# PiPowerRF.net
KiCad netlist of a schematic drawn in EAGLE
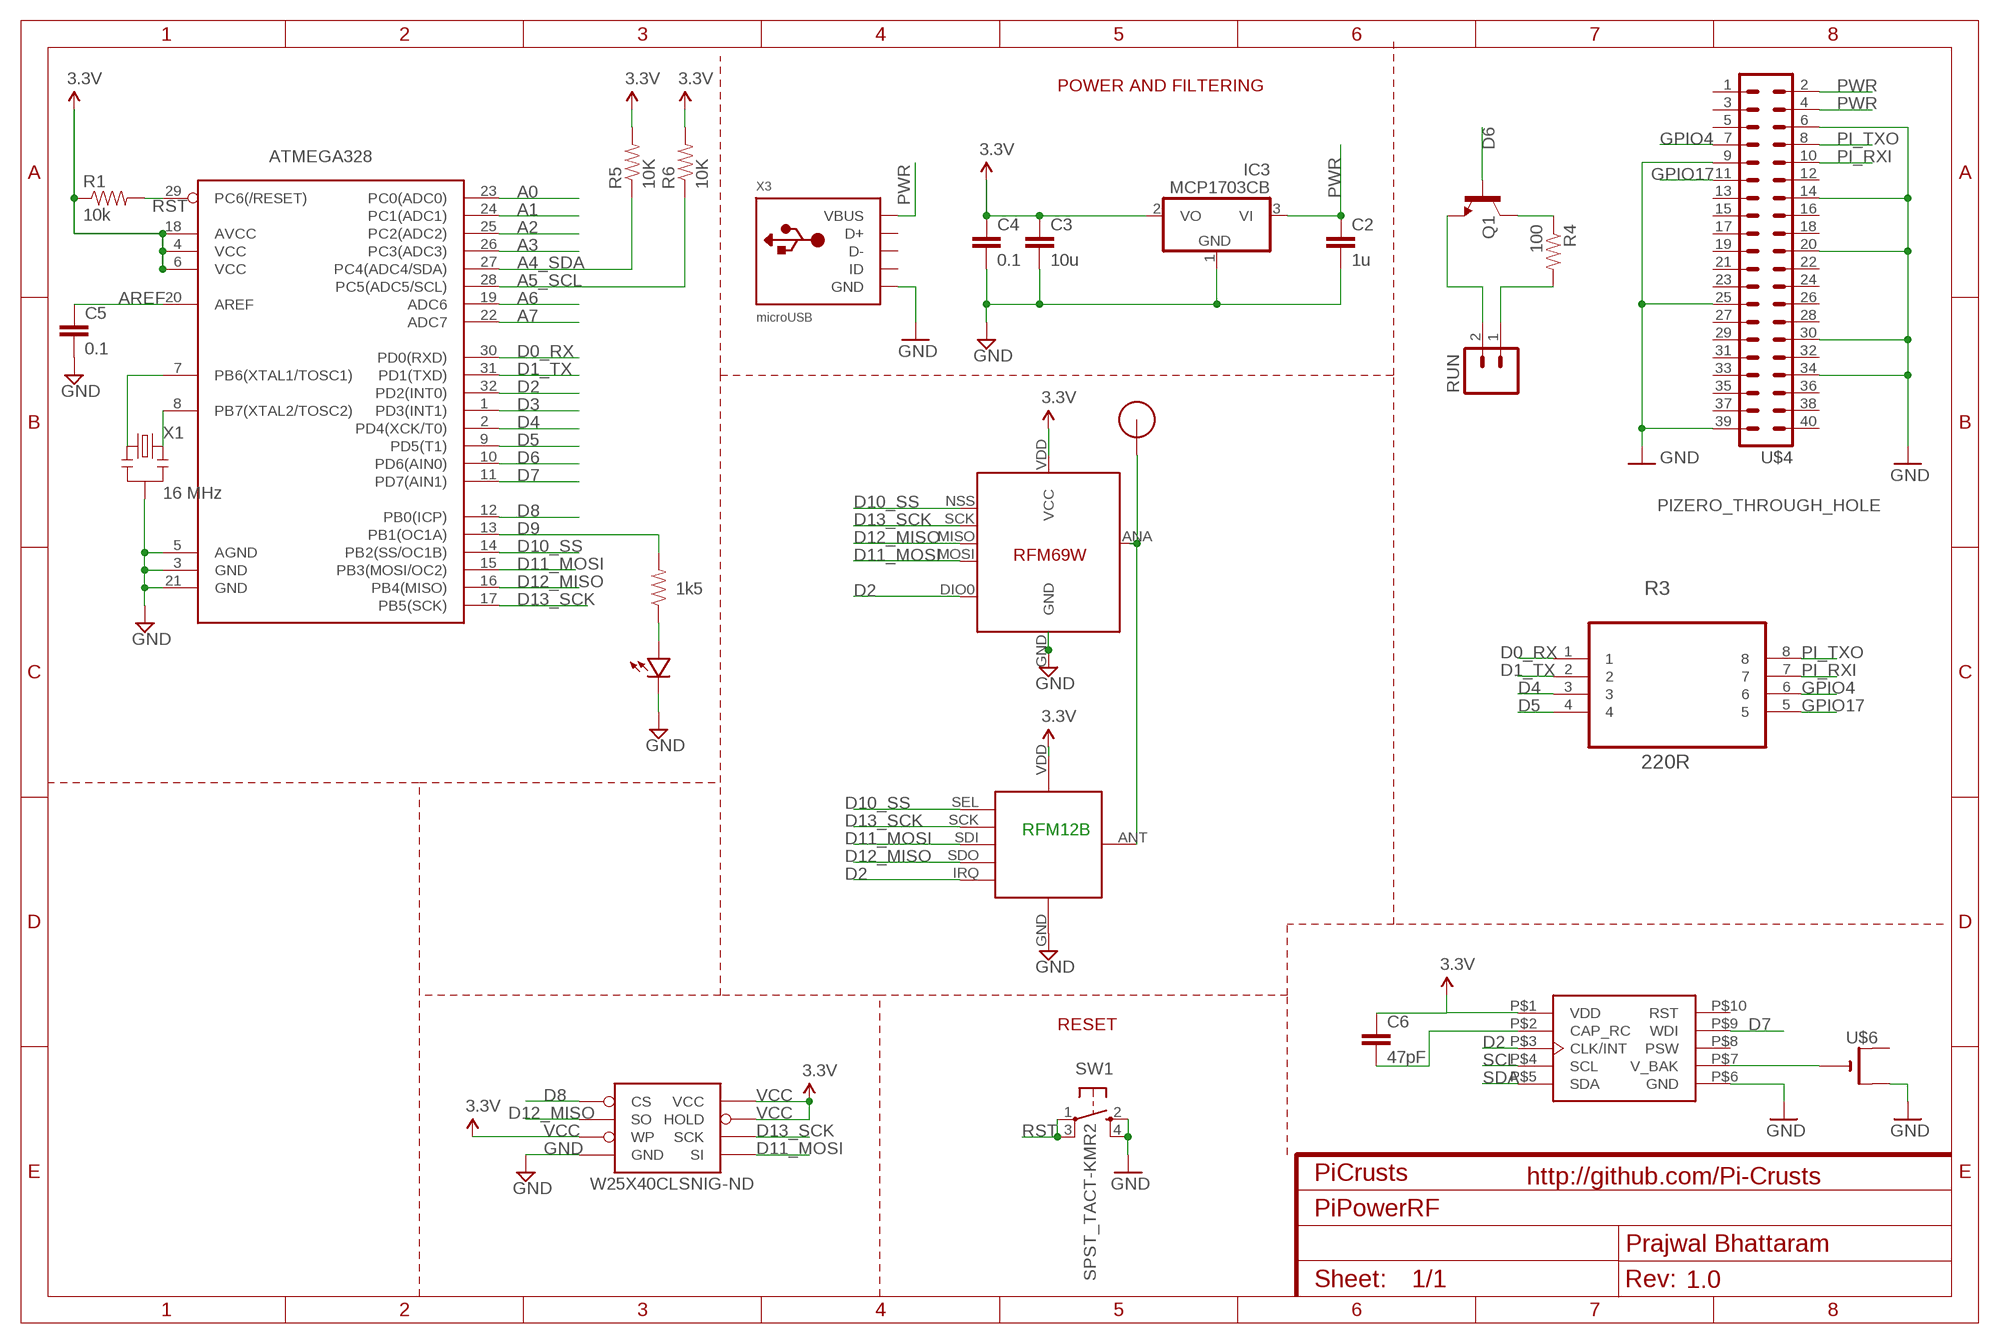
[diagram p0: schematic, sheet 1]

(export (version "E")
  (design (tool "Eeschema 10.0.6"))
  (components
    (comp (ref "ATMEGA328")
      (value "ATMega-328")
      (footprint "eagle-import:TQFP32-08")
      (libsource (lib "eagle-import") (part "ATMEGA168/328TQFP32"))
    )
    (comp (ref "C2")
      (value "1u")
      (footprint "eagle-import:0603-CAP")
      (libsource (lib "eagle-import") (part "CAP0603-CAP"))
    )
    (comp (ref "C3")
      (value "10u")
      (footprint "eagle-import:0805-CAP")
      (libsource (lib "eagle-import") (part "CAP0805-CAP"))
    )
    (comp (ref "C4")
      (value "0.1")
      (footprint "eagle-import:0603-CAP")
      (libsource (lib "eagle-import") (part "CAP0603-CAP"))
    )
    (comp (ref "C5")
      (value "0.1")
      (footprint "eagle-import:0603-CAP")
      (libsource (lib "eagle-import") (part "CAP0603-CAP"))
    )
    (comp (ref "C6")
      (value "47pF")
      (footprint "eagle-import:0402-CAP")
      (libsource (lib "eagle-import") (part "SparkFun-Capacitors_CAP0402-CAP"))
    )
    (comp (ref "IC3")
      (value "MCP1703CB")
      (footprint "eagle-import:SOT23")
      (libsource (lib "eagle-import") (part "MCP1703CB"))
    )
    (comp (ref "Q1")
      (value "MMBT2222A")
      (footprint "eagle-import:SOT23-3")
      (libsource (lib "eagle-import") (part "TRANSISTOR_NPNMMBT2222A"))
    )
    (comp (ref "R1")
      (value "10k")
      (footprint "eagle-import:0603-RES")
      (libsource (lib "eagle-import") (part "RESISTOR0603-RES"))
    )
    (comp (ref "R2")
      (value "1k5")
      (footprint "eagle-import:0603-RES")
      (libsource (lib "eagle-import") (part "RESISTOR0603-RES"))
    )
    (comp (ref "R3")
      (value "220R")
      (footprint "eagle-import:RESCAXE80P320X160X60-8N")
      (fields (field (name "MPN") "EXB38V221JV") (field (name "TOLERANCE") "±5 %"))
      (libsource (lib "eagle-import") (part "EXB38V221JV"))
    )
    (comp (ref "R4")
      (value "100")
      (footprint "eagle-import:0402-RES")
      (libsource (lib "eagle-import") (part "SparkFun-Passives_RESISTOR0402-RES"))
    )
    (comp (ref "R5")
      (value "10K")
      (footprint "eagle-import:0603-RES")
      (libsource (lib "eagle-import") (part "RESISTOR0603"))
    )
    (comp (ref "R6")
      (value "10K")
      (footprint "eagle-import:0603-RES")
      (libsource (lib "eagle-import") (part "RESISTOR0603"))
    )
    (comp (ref "RFM12B")
      (value "RFM12B_MINPADS")
      (footprint "eagle-import:RFM12B-MINPADS")
      (libsource (lib "eagle-import") (part "RFM12B_MINPADS"))
    )
    (comp (ref "RUN")
      (value "M021X02_NO_SILK")
      (footprint "eagle-import:1X02_NO_SILK")
      (libsource (lib "eagle-import") (part "M021X02_NO_SILK"))
    )
    (comp (ref "SW1")
      (value "SPST_TACT-KMR2")
      (footprint "eagle-import:KMR2")
      (libsource (lib "eagle-import") (part "SPST_TACT-KMR2"))
    )
    (comp (ref "U$1")
      (value "RFM12B_ANTENNA")
      (footprint "eagle-import:RFM12B-ANTENNA")
      (libsource (lib "eagle-import") (part "RFM12B_ANTENNA"))
    )
    (comp (ref "U$2")
      (value "LED0603")
      (footprint "eagle-import:0603-LED")
      (libsource (lib "eagle-import") (part "LED0603"))
    )
    (comp (ref "U$4")
      (value "PIZERO_THROUGH_HOLE")
      (footprint "eagle-import:PIZERO_THOUGH_HOLE")
      (libsource (lib "eagle-import") (part "PIZERO_THROUGH_HOLE"))
    )
    (comp (ref "U$5")
      (value "RFM69")
      (footprint "eagle-import:RFM69W-MINPADS")
      (libsource (lib "eagle-import") (part "RFM69"))
    )
    (comp (ref "U$6")
      (value "CR1220SMT")
      (footprint "eagle-import:CR1220-SMD")
      (libsource (lib "eagle-import") (part "CR1220SMT"))
    )
    (comp (ref "W25X40CLSNIG-ND")
      (value "AT25F512BWIDE_5.3MM")
      (footprint "eagle-import:SO08WIDE")
      (libsource (lib "eagle-import") (part "AT25F512BWIDE_5.3MM"))
    )
    (comp (ref "X1")
      (value "16 MHz")
      (footprint "eagle-import:RESONATOR-SMD")
      (libsource (lib "eagle-import") (part "RESONATORSMD"))
    )
    (comp (ref "X2")
      (value "MC-RTC-RV-1805-C3-I2C")
      (footprint "eagle-import:MC-RTC-C3")
      (libsource (lib "eagle-import") (part "MC-RTC-RV-1805-C3-I2C"))
    )
    (comp (ref "X3")
      (value "microUSB")
      (footprint "eagle-import:4UCONN_20329_V2")
      (libsource (lib "eagle-import") (part "USB_MICRO_20329_V2"))
    )
  )
  (nets
    (net (code "1") (name "/A0") (class "Default")
      (node (ref "ATMEGA328") (pin "23") (pinfunction "PC0(ADC0)_23") (pintype "bidirectional"))
    )
    (net (code "2") (name "/A1") (class "Default")
      (node (ref "ATMEGA328") (pin "24") (pinfunction "PC1(ADC1)_24") (pintype "bidirectional"))
    )
    (net (code "3") (name "/A2") (class "Default")
      (node (ref "ATMEGA328") (pin "25") (pinfunction "PC2(ADC2)_25") (pintype "bidirectional"))
    )
    (net (code "4") (name "/A3") (class "Default")
      (node (ref "ATMEGA328") (pin "26") (pinfunction "PC3(ADC3)_26") (pintype "bidirectional"))
    )
    (net (code "5") (name "/A4_SDA") (class "Default")
      (node (ref "ATMEGA328") (pin "27") (pinfunction "PC4(ADC4/SDA)_27") (pintype "bidirectional"))
      (node (ref "R5") (pin "1") (pinfunction "1_1") (pintype "passive"))
    )
    (net (code "6") (name "/A5_SCL") (class "Default")
      (node (ref "ATMEGA328") (pin "28") (pinfunction "PC5(ADC5/SCL)_28") (pintype "bidirectional"))
      (node (ref "R6") (pin "1") (pinfunction "1_1") (pintype "passive"))
    )
    (net (code "7") (name "/A6") (class "Default")
      (node (ref "ATMEGA328") (pin "19") (pinfunction "ADC6_19") (pintype "bidirectional"))
    )
    (net (code "8") (name "/A7") (class "Default")
      (node (ref "ATMEGA328") (pin "22") (pinfunction "ADC7_22") (pintype "bidirectional"))
    )
    (net (code "9") (name "/AREF") (class "Default")
      (node (ref "ATMEGA328") (pin "20") (pinfunction "AREF_20") (pintype "bidirectional"))
      (node (ref "C5") (pin "1") (pinfunction "1_1") (pintype "passive"))
    )
    (net (code "10") (name "/D0_RX") (class "Default")
      (node (ref "ATMEGA328") (pin "30") (pinfunction "PD0(RXD)_30") (pintype "bidirectional"))
      (node (ref "R3") (pin "1") (pinfunction "1_1") (pintype "passive"))
    )
    (net (code "11") (name "/D1_TX") (class "Default")
      (node (ref "ATMEGA328") (pin "31") (pinfunction "PD1(TXD)_31") (pintype "bidirectional"))
      (node (ref "R3") (pin "2") (pinfunction "2_2") (pintype "passive"))
    )
    (net (code "12") (name "/D2") (class "Default")
      (node (ref "ATMEGA328") (pin "32") (pinfunction "PD2(INT0)_32") (pintype "bidirectional"))
      (node (ref "RFM12B") (pin "IRQ") (pinfunction "IRQ_IRQ") (pintype "bidirectional"))
      (node (ref "U$5") (pin "DIO0") (pinfunction "DIO0_DIO0") (pintype "open_collector"))
      (node (ref "X2") (pin "P$3") (pinfunction "CLK/INT_P$3") (pintype "output"))
    )
    (net (code "13") (name "/D3") (class "Default")
      (node (ref "ATMEGA328") (pin "1") (pinfunction "PD3(INT1)_1") (pintype "bidirectional"))
    )
    (net (code "14") (name "/D4") (class "Default")
      (node (ref "ATMEGA328") (pin "2") (pinfunction "PD4(XCK/T0)_2") (pintype "bidirectional"))
      (node (ref "R3") (pin "3") (pinfunction "3_3") (pintype "passive"))
    )
    (net (code "15") (name "/D5") (class "Default")
      (node (ref "ATMEGA328") (pin "9") (pinfunction "PD5(T1)_9") (pintype "bidirectional"))
      (node (ref "R3") (pin "4") (pinfunction "4_4") (pintype "passive"))
    )
    (net (code "16") (name "/D6") (class "Default")
      (node (ref "ATMEGA328") (pin "10") (pinfunction "PD6(AIN0)_10") (pintype "bidirectional"))
      (node (ref "Q1") (pin "1") (pinfunction "B_1") (pintype "passive"))
    )
    (net (code "17") (name "/D7") (class "Default")
      (node (ref "ATMEGA328") (pin "11") (pinfunction "PD7(AIN1)_11") (pintype "bidirectional"))
      (node (ref "X2") (pin "P$9") (pinfunction "WDI_P$9") (pintype "bidirectional"))
    )
    (net (code "18") (name "/D8") (class "Default")
      (node (ref "ATMEGA328") (pin "12") (pinfunction "PB0(ICP)_12") (pintype "bidirectional"))
      (node (ref "W25X40CLSNIG-ND") (pin "1") (pinfunction "CS_1") (pintype "bidirectional"))
    )
    (net (code "19") (name "/D9") (class "Default")
      (node (ref "ATMEGA328") (pin "13") (pinfunction "PB1(OC1A)_13") (pintype "bidirectional"))
      (node (ref "R2") (pin "2") (pinfunction "2_2") (pintype "passive"))
    )
    (net (code "20") (name "/D10_SS") (class "Default")
      (node (ref "ATMEGA328") (pin "14") (pinfunction "PB2(SS/OC1B)_14") (pintype "bidirectional"))
      (node (ref "RFM12B") (pin "SEL") (pinfunction "SEL_SEL") (pintype "bidirectional"))
      (node (ref "U$5") (pin "NSS") (pinfunction "SEL_NSS") (pintype "input"))
    )
    (net (code "21") (name "/D11_MOSI") (class "Default")
      (node (ref "ATMEGA328") (pin "15") (pinfunction "PB3(MOSI/OC2)_15") (pintype "bidirectional"))
      (node (ref "RFM12B") (pin "SDI") (pinfunction "SDI/MOSI_SDI") (pintype "bidirectional"))
      (node (ref "U$5") (pin "MOSI") (pinfunction "MOSI_MOSI") (pintype "output"))
      (node (ref "W25X40CLSNIG-ND") (pin "5") (pinfunction "SI_5") (pintype "bidirectional"))
    )
    (net (code "22") (name "/D12_MISO") (class "Default")
      (node (ref "ATMEGA328") (pin "16") (pinfunction "PB4(MISO)_16") (pintype "bidirectional"))
      (node (ref "RFM12B") (pin "SDO") (pinfunction "SDO/MISO_SDO") (pintype "bidirectional"))
      (node (ref "U$5") (pin "MISO") (pinfunction "MISO_MISO") (pintype "input"))
      (node (ref "W25X40CLSNIG-ND") (pin "2") (pinfunction "SO_2") (pintype "bidirectional"))
    )
    (net (code "23") (name "/D13_SCK") (class "Default")
      (node (ref "ATMEGA328") (pin "17") (pinfunction "PB5(SCK)_17") (pintype "bidirectional"))
      (node (ref "RFM12B") (pin "SCK") (pinfunction "SCK_SCK") (pintype "bidirectional"))
      (node (ref "U$5") (pin "SCK") (pinfunction "SCK_SCK") (pintype "input"))
      (node (ref "W25X40CLSNIG-ND") (pin "6") (pinfunction "SCK_6") (pintype "bidirectional"))
    )
    (net (code "24") (name "/GPIO4") (class "Default")
      (node (ref "R3") (pin "6") (pinfunction "6_6") (pintype "passive"))
      (node (ref "U$4") (pin "7") (pinfunction "7_7") (pintype "passive"))
    )
    (net (code "25") (name "/GPIO17") (class "Default")
      (node (ref "R3") (pin "5") (pinfunction "5_5") (pintype "passive"))
      (node (ref "U$4") (pin "11") (pinfunction "11_11") (pintype "passive"))
    )
    (net (code "26") (name "/PI_RXI") (class "Default")
      (node (ref "R3") (pin "7") (pinfunction "7_7") (pintype "passive"))
      (node (ref "U$4") (pin "10") (pinfunction "10_10") (pintype "passive"))
    )
    (net (code "27") (name "/PI_TXO") (class "Default")
      (node (ref "R3") (pin "8") (pinfunction "8_8") (pintype "passive"))
      (node (ref "U$4") (pin "8") (pinfunction "8_8") (pintype "passive"))
    )
    (net (code "28") (name "/PWR") (class "Default")
      (node (ref "C2") (pin "1") (pinfunction "1_1") (pintype "passive"))
      (node (ref "IC3") (pin "3") (pinfunction "VI_3") (pintype "input"))
      (node (ref "U$4") (pin "2") (pinfunction "2_2") (pintype "passive"))
      (node (ref "U$4") (pin "4") (pinfunction "4_4") (pintype "passive"))
      (node (ref "X3") (pin "VBUS") (pinfunction "VBUS_VBUS") (pintype "power_in"))
    )
    (net (code "29") (name "/RST") (class "Default")
      (node (ref "ATMEGA328") (pin "29") (pinfunction "PC6(/RESET)_29") (pintype "bidirectional"))
      (node (ref "R1") (pin "2") (pinfunction "2_2") (pintype "passive"))
      (node (ref "SW1") (pin "1") (pinfunction "P_1") (pintype "passive"))
      (node (ref "SW1") (pin "3") (pinfunction "P1_3") (pintype "passive"))
    )
    (net (code "30") (name "/SCL") (class "Default")
      (node (ref "X2") (pin "P$4") (pinfunction "SCL_P$4") (pintype "bidirectional"))
    )
    (net (code "31") (name "/SDA") (class "Default")
      (node (ref "X2") (pin "P$5") (pinfunction "SDA_P$5") (pintype "bidirectional"))
    )
    (net (code "32") (name "3.3V") (class "Default")
      (node (ref "ATMEGA328") (pin "18") (pinfunction "AVCC_18") (pintype "bidirectional"))
      (node (ref "ATMEGA328") (pin "4") (pinfunction "VCC_4") (pintype "bidirectional"))
      (node (ref "ATMEGA328") (pin "6") (pinfunction "VCC_6") (pintype "bidirectional"))
      (node (ref "C3") (pin "1") (pinfunction "1_1") (pintype "passive"))
      (node (ref "C4") (pin "1") (pinfunction "1_1") (pintype "passive"))
      (node (ref "C6") (pin "1") (pinfunction "1_1") (pintype "passive"))
      (node (ref "IC3") (pin "2") (pinfunction "VO_2") (pintype "passive"))
      (node (ref "R1") (pin "1") (pinfunction "1_1") (pintype "passive"))
      (node (ref "R5") (pin "2") (pinfunction "2_2") (pintype "passive"))
      (node (ref "R6") (pin "2") (pinfunction "2_2") (pintype "passive"))
      (node (ref "RFM12B") (pin "VDD") (pinfunction "VDD_VDD") (pintype "bidirectional"))
      (node (ref "U$5") (pin "VDD") (pinfunction "VCC_VDD") (pintype "power_in"))
      (node (ref "W25X40CLSNIG-ND") (pin "3") (pinfunction "WP_3") (pintype "bidirectional"))
      (node (ref "W25X40CLSNIG-ND") (pin "7") (pinfunction "HOLD_7") (pintype "bidirectional"))
      (node (ref "W25X40CLSNIG-ND") (pin "8") (pinfunction "VCC_8") (pintype "bidirectional"))
      (node (ref "X2") (pin "P$1") (pinfunction "VDD_P$1") (pintype "power_in"))
    )
    (net (code "33") (name "GND") (class "Default")
      (node (ref "ATMEGA328") (pin "21") (pinfunction "GND_21") (pintype "bidirectional"))
      (node (ref "ATMEGA328") (pin "3") (pinfunction "GND_3") (pintype "bidirectional"))
      (node (ref "ATMEGA328") (pin "5") (pinfunction "AGND_5") (pintype "bidirectional"))
      (node (ref "C2") (pin "2") (pinfunction "2_2") (pintype "passive"))
      (node (ref "C3") (pin "2") (pinfunction "2_2") (pintype "passive"))
      (node (ref "C4") (pin "2") (pinfunction "2_2") (pintype "passive"))
      (node (ref "C5") (pin "2") (pinfunction "2_2") (pintype "passive"))
      (node (ref "IC3") (pin "1") (pinfunction "GND_1") (pintype "passive"))
      (node (ref "RFM12B") (pin "GND") (pinfunction "GND_GND") (pintype "bidirectional"))
      (node (ref "SW1") (pin "2") (pinfunction "S_2") (pintype "passive"))
      (node (ref "SW1") (pin "4") (pinfunction "S1_4") (pintype "passive"))
      (node (ref "U$2") (pin "MINUS") (pinfunction "MINUS_MINUS") (pintype "passive"))
      (node (ref "U$4") (pin "14") (pinfunction "14_14") (pintype "passive"))
      (node (ref "U$4") (pin "20") (pinfunction "20_20") (pintype "passive"))
      (node (ref "U$4") (pin "25") (pinfunction "25_25") (pintype "passive"))
      (node (ref "U$4") (pin "30") (pinfunction "30_30") (pintype "passive"))
      (node (ref "U$4") (pin "34") (pinfunction "34_34") (pintype "passive"))
      (node (ref "U$4") (pin "39") (pinfunction "39_39") (pintype "passive"))
      (node (ref "U$4") (pin "6") (pinfunction "6_6") (pintype "passive"))
      (node (ref "U$4") (pin "9") (pinfunction "9_9") (pintype "passive"))
      (node (ref "U$5") (pin "GND") (pinfunction "GND_GND") (pintype "power_in"))
      (node (ref "U$6") (pin "+$2") (pinfunction "+1_+$2") (pintype "passive"))
      (node (ref "W25X40CLSNIG-ND") (pin "4") (pinfunction "GND_4") (pintype "bidirectional"))
      (node (ref "X1") (pin "2") (pinfunction "2_2") (pintype "passive"))
      (node (ref "X2") (pin "P$6") (pinfunction "GND_P$6") (pintype "power_in"))
      (node (ref "X3") (pin "BASE@1") (pinfunction "GND_BASE@1") (pintype "power_in"))
      (node (ref "X3") (pin "BASE@2") (pinfunction "GND_BASE@2") (pintype "power_in"))
      (node (ref "X3") (pin "GND") (pinfunction "GND_GND") (pintype "power_in"))
      (node (ref "X3") (pin "SPRT@1") (pinfunction "GND_SPRT@1") (pintype "power_in"))
      (node (ref "X3") (pin "SPRT@2") (pinfunction "GND_SPRT@2") (pintype "power_in"))
      (node (ref "X3") (pin "SPRT@3") (pinfunction "GND_SPRT@3") (pintype "power_in"))
      (node (ref "X3") (pin "SPRT@4") (pinfunction "GND_SPRT@4") (pintype "power_in"))
    )
    (net (code "34") (name "Net-(ATMEGA328-PB6(XTAL1{slash}TOSC1))") (class "Default")
      (node (ref "ATMEGA328") (pin "7") (pinfunction "PB6(XTAL1/TOSC1)_7") (pintype "bidirectional"))
      (node (ref "X1") (pin "1") (pinfunction "1_1") (pintype "passive"))
    )
    (net (code "35") (name "Net-(ATMEGA328-PB7(XTAL2{slash}TOSC2))") (class "Default")
      (node (ref "ATMEGA328") (pin "8") (pinfunction "PB7(XTAL2/TOSC2)_8") (pintype "bidirectional"))
      (node (ref "X1") (pin "3") (pinfunction "3_3") (pintype "passive"))
    )
    (net (code "36") (name "Net-(Q1-C)") (class "Default")
      (node (ref "Q1") (pin "3") (pinfunction "C_3") (pintype "passive"))
      (node (ref "R4") (pin "1") (pinfunction "1_1") (pintype "passive"))
    )
    (net (code "37") (name "Net-(Q1-E)") (class "Default")
      (node (ref "Q1") (pin "2") (pinfunction "E_2") (pintype "passive"))
      (node (ref "RUN") (pin "2") (pinfunction "2_2") (pintype "passive"))
    )
    (net (code "38") (name "Net-(R2-Pad1)") (class "Default")
      (node (ref "R2") (pin "1") (pinfunction "1_1") (pintype "passive"))
      (node (ref "U$2") (pin "PLUS") (pinfunction "PLUS_PLUS") (pintype "passive"))
    )
    (net (code "39") (name "Net-(R4-Pad2)") (class "Default")
      (node (ref "R4") (pin "2") (pinfunction "2_2") (pintype "passive"))
      (node (ref "RUN") (pin "1") (pinfunction "1_1") (pintype "passive"))
    )
    (net (code "40") (name "Net-(U$1-1)") (class "Default")
      (node (ref "RFM12B") (pin "ANT") (pinfunction "ANT_ANT") (pintype "bidirectional"))
      (node (ref "U$1") (pin "P$1") (pinfunction "1_P$1") (pintype "bidirectional"))
      (node (ref "U$5") (pin "ANA") (pinfunction "ANT_ANA") (pintype "passive"))
    )
    (net (code "41") (name "Net-(X2-CAP_RC)") (class "Default")
      (node (ref "C6") (pin "2") (pinfunction "2_2") (pintype "passive"))
      (node (ref "X2") (pin "P$2") (pinfunction "CAP_RC_P$2") (pintype "bidirectional"))
    )
    (net (code "42") (name "Net-(X2-V_BAK)") (class "Default")
      (node (ref "U$6") (pin "-") (pinfunction "-_-") (pintype "passive"))
      (node (ref "X2") (pin "P$7") (pinfunction "V_BAK_P$7") (pintype "power_in"))
    )
    (net (code "43") (name "unconnected-(U$4-Pad1)") (class "Default")
      (node (ref "U$4") (pin "1") (pinfunction "1_1") (pintype "passive"))
    )
    (net (code "44") (name "unconnected-(U$4-Pad3)") (class "Default")
      (node (ref "U$4") (pin "3") (pinfunction "3_3") (pintype "passive"))
    )
    (net (code "45") (name "unconnected-(U$4-Pad5)") (class "Default")
      (node (ref "U$4") (pin "5") (pinfunction "5_5") (pintype "passive"))
    )
    (net (code "46") (name "unconnected-(U$4-Pad12)") (class "Default")
      (node (ref "U$4") (pin "12") (pinfunction "12_12") (pintype "passive"))
    )
    (net (code "47") (name "unconnected-(U$4-Pad13)") (class "Default")
      (node (ref "U$4") (pin "13") (pinfunction "13_13") (pintype "passive"))
    )
    (net (code "48") (name "unconnected-(U$4-Pad15)") (class "Default")
      (node (ref "U$4") (pin "15") (pinfunction "15_15") (pintype "passive"))
    )
    (net (code "49") (name "unconnected-(U$4-Pad16)") (class "Default")
      (node (ref "U$4") (pin "16") (pinfunction "16_16") (pintype "passive"))
    )
    (net (code "50") (name "unconnected-(U$4-Pad17)") (class "Default")
      (node (ref "U$4") (pin "17") (pinfunction "17_17") (pintype "passive"))
    )
    (net (code "51") (name "unconnected-(U$4-Pad18)") (class "Default")
      (node (ref "U$4") (pin "18") (pinfunction "18_18") (pintype "passive"))
    )
    (net (code "52") (name "unconnected-(U$4-Pad19)") (class "Default")
      (node (ref "U$4") (pin "19") (pinfunction "19_19") (pintype "passive"))
    )
    (net (code "53") (name "unconnected-(U$4-Pad21)") (class "Default")
      (node (ref "U$4") (pin "21") (pinfunction "21_21") (pintype "passive"))
    )
    (net (code "54") (name "unconnected-(U$4-Pad22)") (class "Default")
      (node (ref "U$4") (pin "22") (pinfunction "22_22") (pintype "passive"))
    )
    (net (code "55") (name "unconnected-(U$4-Pad23)") (class "Default")
      (node (ref "U$4") (pin "23") (pinfunction "23_23") (pintype "passive"))
    )
    (net (code "56") (name "unconnected-(U$4-Pad24)") (class "Default")
      (node (ref "U$4") (pin "24") (pinfunction "24_24") (pintype "passive"))
    )
    (net (code "57") (name "unconnected-(U$4-Pad26)") (class "Default")
      (node (ref "U$4") (pin "26") (pinfunction "26_26") (pintype "passive"))
    )
    (net (code "58") (name "unconnected-(U$4-Pad27)") (class "Default")
      (node (ref "U$4") (pin "27") (pinfunction "27_27") (pintype "passive"))
    )
    (net (code "59") (name "unconnected-(U$4-Pad28)") (class "Default")
      (node (ref "U$4") (pin "28") (pinfunction "28_28") (pintype "passive"))
    )
    (net (code "60") (name "unconnected-(U$4-Pad29)") (class "Default")
      (node (ref "U$4") (pin "29") (pinfunction "29_29") (pintype "passive"))
    )
    (net (code "61") (name "unconnected-(U$4-Pad31)") (class "Default")
      (node (ref "U$4") (pin "31") (pinfunction "31_31") (pintype "passive"))
    )
    (net (code "62") (name "unconnected-(U$4-Pad32)") (class "Default")
      (node (ref "U$4") (pin "32") (pinfunction "32_32") (pintype "passive"))
    )
    (net (code "63") (name "unconnected-(U$4-Pad33)") (class "Default")
      (node (ref "U$4") (pin "33") (pinfunction "33_33") (pintype "passive"))
    )
    (net (code "64") (name "unconnected-(U$4-Pad35)") (class "Default")
      (node (ref "U$4") (pin "35") (pinfunction "35_35") (pintype "passive"))
    )
    (net (code "65") (name "unconnected-(U$4-Pad36)") (class "Default")
      (node (ref "U$4") (pin "36") (pinfunction "36_36") (pintype "passive"))
    )
    (net (code "66") (name "unconnected-(U$4-Pad37)") (class "Default")
      (node (ref "U$4") (pin "37") (pinfunction "37_37") (pintype "passive"))
    )
    (net (code "67") (name "unconnected-(U$4-Pad38)") (class "Default")
      (node (ref "U$4") (pin "38") (pinfunction "38_38") (pintype "passive"))
    )
    (net (code "68") (name "unconnected-(U$4-Pad40)") (class "Default")
      (node (ref "U$4") (pin "40") (pinfunction "40_40") (pintype "passive"))
    )
    (net (code "69") (name "unconnected-(U$6-+-Pad+$1)") (class "Default")
      (node (ref "U$6") (pin "+$1") (pinfunction "+_+$1") (pintype "passive"))
    )
    (net (code "70") (name "unconnected-(X2-PSW-PadP$8)") (class "Default")
      (node (ref "X2") (pin "P$8") (pinfunction "PSW_P$8") (pintype "bidirectional"))
    )
    (net (code "71") (name "unconnected-(X2-RST-PadP$10)") (class "Default")
      (node (ref "X2") (pin "P$10") (pinfunction "RST_P$10") (pintype "bidirectional"))
    )
    (net (code "72") (name "unconnected-(X3-PadD+)") (class "Default")
      (node (ref "X3") (pin "D+") (pinfunction "D+_D+") (pintype "bidirectional"))
    )
    (net (code "73") (name "unconnected-(X3-PadD-)") (class "Default")
      (node (ref "X3") (pin "D-") (pinfunction "D-_D-") (pintype "bidirectional"))
    )
    (net (code "74") (name "unconnected-(X3-PadID)") (class "Default")
      (node (ref "X3") (pin "ID") (pinfunction "ID_ID") (pintype "bidirectional"))
    )
  )
)
